# XmegaA4U_v1.net
KiCad netlist of a schematic drawn in EAGLE
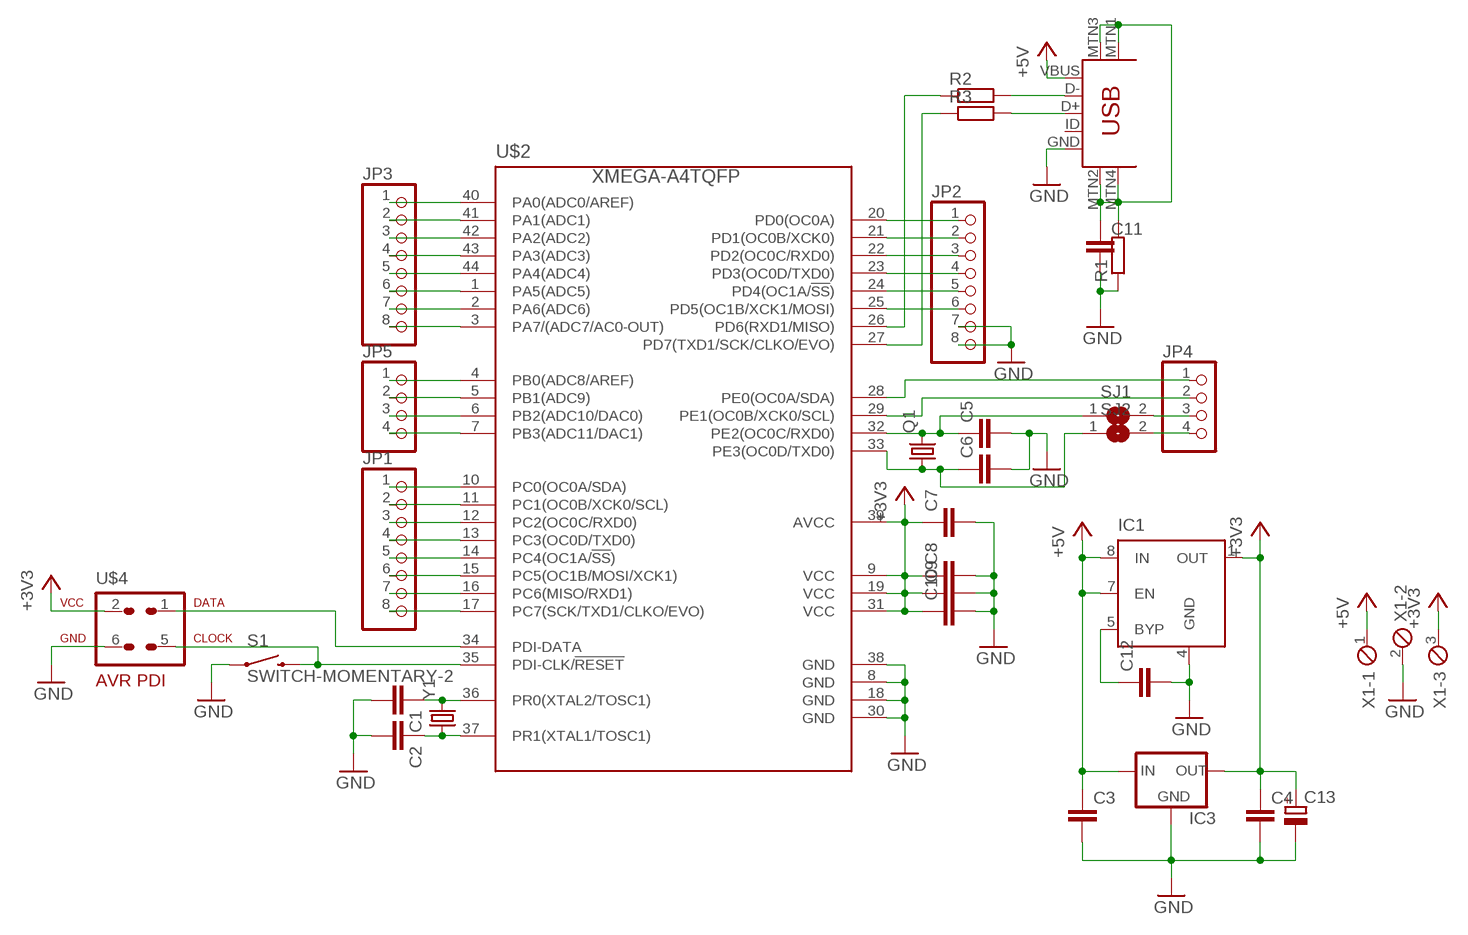
[diagram p0: schematic, sheet 1]

(export (version "E")
  (design (tool "Eeschema 10.0.6"))
  (components
    (comp (ref "C1")
      (value "C-EUC0603")
      (footprint "eagle-import:C0603")
      (libsource (lib "eagle-import") (part "C-EUC0603"))
    )
    (comp (ref "C2")
      (value "C-EUC0603")
      (footprint "eagle-import:C0603")
      (libsource (lib "eagle-import") (part "C-EUC0603"))
    )
    (comp (ref "C3")
      (value "C-EUC0805")
      (footprint "eagle-import:C0805")
      (libsource (lib "eagle-import") (part "C-EUC0805"))
    )
    (comp (ref "C4")
      (value "C-EUC0805")
      (footprint "eagle-import:C0805")
      (libsource (lib "eagle-import") (part "C-EUC0805"))
    )
    (comp (ref "C5")
      (value "C-EUC0603")
      (footprint "eagle-import:C0603")
      (libsource (lib "eagle-import") (part "C-EUC0603"))
    )
    (comp (ref "C6")
      (value "C-EUC0603")
      (footprint "eagle-import:C0603")
      (libsource (lib "eagle-import") (part "C-EUC0603"))
    )
    (comp (ref "C7")
      (value "C-EUC0603")
      (footprint "eagle-import:C0603")
      (libsource (lib "eagle-import") (part "C-EUC0603"))
    )
    (comp (ref "C8")
      (value "C-EUC0603")
      (footprint "eagle-import:C0603")
      (libsource (lib "eagle-import") (part "C-EUC0603"))
    )
    (comp (ref "C9")
      (value "C-EUC0603")
      (footprint "eagle-import:C0603")
      (libsource (lib "eagle-import") (part "C-EUC0603"))
    )
    (comp (ref "C10")
      (value "C-EUC0603")
      (footprint "eagle-import:C0603")
      (libsource (lib "eagle-import") (part "C-EUC0603"))
    )
    (comp (ref "C11")
      (value "C-EUC0603")
      (footprint "eagle-import:C0603")
      (libsource (lib "eagle-import") (part "C-EUC0603"))
    )
    (comp (ref "C12")
      (value "C-EUC0603")
      (footprint "eagle-import:C0603")
      (libsource (lib "eagle-import") (part "C-EUC0603"))
    )
    (comp (ref "C13")
      (value "CPOL-EUSMCB")
      (footprint "eagle-import:SMC_B")
      (libsource (lib "eagle-import") (part "CPOL-EUSMCB"))
    )
    (comp (ref "IC1")
      (value "TC1269")
      (footprint "eagle-import:MSOP08")
      (libsource (lib "eagle-import") (part "TC1269"))
    )
    (comp (ref "IC3")
      (value "VREG_3PIN_O-G-ITO92_MID")
      (footprint "eagle-import:TO92_MID")
      (libsource (lib "eagle-import") (part "VREG_3PIN_O-G-ITO92_MID"))
    )
    (comp (ref "JP1")
      (value "PINHD_FIXEDPAD_ROUND-1X8")
      (footprint "eagle-import:1X08_ROUND")
      (libsource (lib "eagle-import") (part "PINHD_FIXEDPAD_ROUND-1X8"))
    )
    (comp (ref "JP2")
      (value "PINHD_FIXEDPAD_ROUND-1X8")
      (footprint "eagle-import:1X08_ROUND")
      (libsource (lib "eagle-import") (part "PINHD_FIXEDPAD_ROUND-1X8"))
    )
    (comp (ref "JP3")
      (value "PINHD_FIXEDPAD_ROUND-1X8")
      (footprint "eagle-import:1X08_ROUND")
      (libsource (lib "eagle-import") (part "PINHD_FIXEDPAD_ROUND-1X8"))
    )
    (comp (ref "JP4")
      (value "PINHD_FIXEDPAD_ROUND-1X4")
      (footprint "eagle-import:1X04_ROUND")
      (libsource (lib "eagle-import") (part "PINHD_FIXEDPAD_ROUND-1X4"))
    )
    (comp (ref "JP5")
      (value "PINHD_FIXEDPAD_ROUND-1X4")
      (footprint "eagle-import:1X04_ROUND")
      (libsource (lib "eagle-import") (part "PINHD_FIXEDPAD_ROUND-1X4"))
    )
    (comp (ref "Q1")
      (value "CRYSTALTC26V")
      (footprint "eagle-import:TC26V")
      (libsource (lib "eagle-import") (part "CRYSTALTC26V"))
    )
    (comp (ref "R1")
      (value "R-EU_R0603")
      (footprint "eagle-import:R0603")
      (libsource (lib "eagle-import") (part "R-EU_R0603"))
    )
    (comp (ref "R2")
      (value "R-EU_R0603")
      (footprint "eagle-import:R0603")
      (libsource (lib "eagle-import") (part "R-EU_R0603"))
    )
    (comp (ref "R3")
      (value "R-EU_R0603")
      (footprint "eagle-import:R0603")
      (libsource (lib "eagle-import") (part "R-EU_R0603"))
    )
    (comp (ref "S1")
      (value "SWITCH-MOMENTARY-2")
      (footprint "eagle-import:TACTILE_SWITCH_TALL")
      (libsource (lib "eagle-import") (part "SWITCH-MOMENTARY-2"))
    )
    (comp (ref "SJ1")
      (value "SJ_SMALL")
      (footprint "eagle-import:SJ_2S-NO")
      (libsource (lib "eagle-import") (part "SJ_SMALL"))
    )
    (comp (ref "SJ2")
      (value "SJ_SMALL")
      (footprint "eagle-import:SJ_2S-NO")
      (libsource (lib "eagle-import") (part "SJ_SMALL"))
    )
    (comp (ref "U$1")
      (value "USB-MINIB-5PIN")
      (footprint "eagle-import:USB-MINIB")
      (libsource (lib "eagle-import") (part "USB-MINIB-5PIN"))
    )
    (comp (ref "U$2")
      (value "XMEGA-A4TQFP")
      (footprint "eagle-import:TQFP44")
      (libsource (lib "eagle-import") (part "XMEGA-A4TQFP"))
    )
    (comp (ref "U$4")
      (value "AVR-PDIVERT")
      (footprint "eagle-import:AVR-ISP-6")
      (libsource (lib "eagle-import") (part "AVR-PDIVERT"))
    )
    (comp (ref "X1")
      (value "MPT3")
      (footprint "eagle-import:3POL254")
      (libsource (lib "eagle-import") (part "MPT3"))
    )
    (comp (ref "Y1")
      (value "CRYSTAL5X3")
      (footprint "eagle-import:CRYSTAL-SMD-5X3")
      (libsource (lib "eagle-import") (part "CRYSTAL5X3"))
    )
  )
  (nets
    (net (code "1") (name "+3V3") (class "Default")
      (node (ref "C10") (pin "1") (pinfunction "1_1") (pintype "passive"))
      (node (ref "C13") (pin "+") (pinfunction "+_+") (pintype "passive"))
      (node (ref "C4") (pin "1") (pinfunction "1_1") (pintype "passive"))
      (node (ref "C7") (pin "1") (pinfunction "1_1") (pintype "passive"))
      (node (ref "C8") (pin "1") (pinfunction "1_1") (pintype "passive"))
      (node (ref "C9") (pin "1") (pinfunction "1_1") (pintype "passive"))
      (node (ref "IC1") (pin "1") (pinfunction "OUT_1") (pintype "output"))
      (node (ref "IC3") (pin "1") (pinfunction "OUT_1") (pintype "output"))
      (node (ref "U$2") (pin "19") (pinfunction "VCC_19") (pintype "power_in"))
      (node (ref "U$2") (pin "31") (pinfunction "VCC_31") (pintype "power_in"))
      (node (ref "U$2") (pin "39") (pinfunction "AVCC_39") (pintype "power_in"))
      (node (ref "U$2") (pin "9") (pinfunction "VCC_9") (pintype "power_in"))
      (node (ref "U$4") (pin "2") (pinfunction "2_2") (pintype "passive"))
      (node (ref "X1") (pin "3") (pinfunction "1_3") (pintype "passive"))
    )
    (net (code "2") (name "+5V") (class "Default")
      (node (ref "C3") (pin "1") (pinfunction "1_1") (pintype "passive"))
      (node (ref "IC1") (pin "7") (pinfunction "EN_7") (pintype "input"))
      (node (ref "IC1") (pin "8") (pinfunction "IN_8") (pintype "input"))
      (node (ref "IC3") (pin "3") (pinfunction "IN_3") (pintype "input"))
      (node (ref "U$1") (pin "VBUS") (pinfunction "VBUS_VBUS") (pintype "bidirectional"))
      (node (ref "X1") (pin "1") (pinfunction "1_1") (pintype "passive"))
    )
    (net (code "3") (name "GND") (class "Default")
      (node (ref "C1") (pin "2") (pinfunction "2_2") (pintype "passive"))
      (node (ref "C10") (pin "2") (pinfunction "2_2") (pintype "passive"))
      (node (ref "C11") (pin "2") (pinfunction "2_2") (pintype "passive"))
      (node (ref "C12") (pin "2") (pinfunction "2_2") (pintype "passive"))
      (node (ref "C13") (pin "-") (pinfunction "-_-") (pintype "passive"))
      (node (ref "C2") (pin "2") (pinfunction "2_2") (pintype "passive"))
      (node (ref "C3") (pin "2") (pinfunction "2_2") (pintype "passive"))
      (node (ref "C4") (pin "2") (pinfunction "2_2") (pintype "passive"))
      (node (ref "C5") (pin "2") (pinfunction "2_2") (pintype "passive"))
      (node (ref "C6") (pin "2") (pinfunction "2_2") (pintype "passive"))
      (node (ref "C7") (pin "2") (pinfunction "2_2") (pintype "passive"))
      (node (ref "C8") (pin "2") (pinfunction "2_2") (pintype "passive"))
      (node (ref "C9") (pin "2") (pinfunction "2_2") (pintype "passive"))
      (node (ref "IC1") (pin "4") (pinfunction "GND_4") (pintype "power_in"))
      (node (ref "IC3") (pin "2") (pinfunction "GND_2") (pintype "input"))
      (node (ref "JP2") (pin "7") (pinfunction "7_7") (pintype "passive"))
      (node (ref "JP2") (pin "8") (pinfunction "8_8") (pintype "passive"))
      (node (ref "R1") (pin "1") (pinfunction "1_1") (pintype "passive"))
      (node (ref "S1") (pin "A2") (pinfunction "1_A2") (pintype "passive"))
      (node (ref "U$1") (pin "GND") (pinfunction "GND_GND") (pintype "bidirectional"))
      (node (ref "U$2") (pin "18") (pinfunction "GND_18") (pintype "power_in"))
      (node (ref "U$2") (pin "30") (pinfunction "GND_30") (pintype "power_in"))
      (node (ref "U$2") (pin "38") (pinfunction "GND_38") (pintype "power_in"))
      (node (ref "U$2") (pin "8") (pinfunction "GND_8") (pintype "power_in"))
      (node (ref "U$4") (pin "6") (pinfunction "6_6") (pintype "passive"))
      (node (ref "X1") (pin "2") (pinfunction "1_2") (pintype "passive"))
    )
    (net (code "4") (name "Net-(IC1-BYP)") (class "Default")
      (node (ref "C12") (pin "1") (pinfunction "1_1") (pintype "passive"))
      (node (ref "IC1") (pin "5") (pinfunction "BYP_5") (pintype "passive"))
    )
    (net (code "5") (name "Net-(JP4-Pad3)") (class "Default")
      (node (ref "JP4") (pin "3") (pinfunction "3_3") (pintype "passive"))
      (node (ref "SJ1") (pin "2") (pinfunction "2_2") (pintype "passive"))
    )
    (net (code "6") (name "Net-(JP4-Pad4)") (class "Default")
      (node (ref "JP4") (pin "4") (pinfunction "4_4") (pintype "passive"))
      (node (ref "SJ2") (pin "2") (pinfunction "2_2") (pintype "passive"))
    )
    (net (code "7") (name "Net-(R2-Pad2)") (class "Default")
      (node (ref "R2") (pin "2") (pinfunction "2_2") (pintype "passive"))
      (node (ref "U$1") (pin "D-") (pinfunction "D-_D-") (pintype "bidirectional"))
    )
    (net (code "8") (name "Net-(R3-Pad2)") (class "Default")
      (node (ref "R3") (pin "2") (pinfunction "2_2") (pintype "passive"))
      (node (ref "U$1") (pin "D+") (pinfunction "D+_D+") (pintype "bidirectional"))
    )
    (net (code "9") (name "Net-(S1-2)") (class "Default")
      (node (ref "S1") (pin "B2") (pinfunction "2_B2") (pintype "passive"))
      (node (ref "U$2") (pin "35") (pinfunction "PDI-CLK/~{RESET}_35") (pintype "input"))
      (node (ref "U$4") (pin "5") (pinfunction "5_5") (pintype "passive"))
    )
    (net (code "10") (name "Net-(U$1-MTN1)") (class "Default")
      (node (ref "C11") (pin "1") (pinfunction "1_1") (pintype "passive"))
      (node (ref "R1") (pin "2") (pinfunction "2_2") (pintype "passive"))
      (node (ref "U$1") (pin "MTN1") (pinfunction "MTN2_MTN1") (pintype "bidirectional"))
      (node (ref "U$1") (pin "MTN2") (pinfunction "MTN3_MTN2") (pintype "bidirectional"))
      (node (ref "U$1") (pin "MTN3") (pinfunction "MTN1_MTN3") (pintype "bidirectional"))
      (node (ref "U$1") (pin "MTN4") (pinfunction "MTN4_MTN4") (pintype "bidirectional"))
    )
    (net (code "11") (name "Net-(U$2-PA0(ADC0{slash}AREF))") (class "Default")
      (node (ref "JP3") (pin "1") (pinfunction "1_1") (pintype "passive"))
      (node (ref "U$2") (pin "40") (pinfunction "PA0(ADC0/AREF)_40") (pintype "bidirectional"))
    )
    (net (code "12") (name "Net-(U$2-PA1(ADC1))") (class "Default")
      (node (ref "JP3") (pin "2") (pinfunction "2_2") (pintype "passive"))
      (node (ref "U$2") (pin "41") (pinfunction "PA1(ADC1)_41") (pintype "bidirectional"))
    )
    (net (code "13") (name "Net-(U$2-PA2(ADC2))") (class "Default")
      (node (ref "JP3") (pin "3") (pinfunction "3_3") (pintype "passive"))
      (node (ref "U$2") (pin "42") (pinfunction "PA2(ADC2)_42") (pintype "bidirectional"))
    )
    (net (code "14") (name "Net-(U$2-PA3(ADC3))") (class "Default")
      (node (ref "JP3") (pin "4") (pinfunction "4_4") (pintype "passive"))
      (node (ref "U$2") (pin "43") (pinfunction "PA3(ADC3)_43") (pintype "bidirectional"))
    )
    (net (code "15") (name "Net-(U$2-PA4(ADC4))") (class "Default")
      (node (ref "JP3") (pin "5") (pinfunction "5_5") (pintype "passive"))
      (node (ref "U$2") (pin "44") (pinfunction "PA4(ADC4)_44") (pintype "bidirectional"))
    )
    (net (code "16") (name "Net-(U$2-PA5(ADC5))") (class "Default")
      (node (ref "JP3") (pin "6") (pinfunction "6_6") (pintype "passive"))
      (node (ref "U$2") (pin "1") (pinfunction "PA5(ADC5)_1") (pintype "bidirectional"))
    )
    (net (code "17") (name "Net-(U$2-PA6(ADC6))") (class "Default")
      (node (ref "JP3") (pin "7") (pinfunction "7_7") (pintype "passive"))
      (node (ref "U$2") (pin "2") (pinfunction "PA6(ADC6)_2") (pintype "bidirectional"))
    )
    (net (code "18") (name "Net-(U$2-PA7{slash}(ADC7{slash}AC0-OUT))") (class "Default")
      (node (ref "JP3") (pin "8") (pinfunction "8_8") (pintype "passive"))
      (node (ref "U$2") (pin "3") (pinfunction "PA7/(ADC7/AC0-OUT)_3") (pintype "bidirectional"))
    )
    (net (code "19") (name "Net-(U$2-PB0(ADC8{slash}AREF))") (class "Default")
      (node (ref "JP5") (pin "1") (pinfunction "1_1") (pintype "passive"))
      (node (ref "U$2") (pin "4") (pinfunction "PB0(ADC8/AREF)_4") (pintype "bidirectional"))
    )
    (net (code "20") (name "Net-(U$2-PB1(ADC9))") (class "Default")
      (node (ref "JP5") (pin "2") (pinfunction "2_2") (pintype "passive"))
      (node (ref "U$2") (pin "5") (pinfunction "PB1(ADC9)_5") (pintype "bidirectional"))
    )
    (net (code "21") (name "Net-(U$2-PB2(ADC10{slash}DAC0))") (class "Default")
      (node (ref "JP5") (pin "3") (pinfunction "3_3") (pintype "passive"))
      (node (ref "U$2") (pin "6") (pinfunction "PB2(ADC10/DAC0)_6") (pintype "bidirectional"))
    )
    (net (code "22") (name "Net-(U$2-PB3(ADC11{slash}DAC1))") (class "Default")
      (node (ref "JP5") (pin "4") (pinfunction "4_4") (pintype "passive"))
      (node (ref "U$2") (pin "7") (pinfunction "PB3(ADC11/DAC1)_7") (pintype "bidirectional"))
    )
    (net (code "23") (name "Net-(U$2-PC0(OC0A{slash}SDA))") (class "Default")
      (node (ref "JP1") (pin "1") (pinfunction "1_1") (pintype "passive"))
      (node (ref "U$2") (pin "10") (pinfunction "PC0(OC0A/SDA)_10") (pintype "bidirectional"))
    )
    (net (code "24") (name "Net-(U$2-PC1(OC0B{slash}XCK0{slash}SCL))") (class "Default")
      (node (ref "JP1") (pin "2") (pinfunction "2_2") (pintype "passive"))
      (node (ref "U$2") (pin "11") (pinfunction "PC1(OC0B/XCK0/SCL)_11") (pintype "bidirectional"))
    )
    (net (code "25") (name "Net-(U$2-PC2(OC0C{slash}RXD0))") (class "Default")
      (node (ref "JP1") (pin "3") (pinfunction "3_3") (pintype "passive"))
      (node (ref "U$2") (pin "12") (pinfunction "PC2(OC0C/RXD0)_12") (pintype "bidirectional"))
    )
    (net (code "26") (name "Net-(U$2-PC3(OC0D{slash}TXD0))") (class "Default")
      (node (ref "JP1") (pin "4") (pinfunction "4_4") (pintype "passive"))
      (node (ref "U$2") (pin "13") (pinfunction "PC3(OC0D/TXD0)_13") (pintype "bidirectional"))
    )
    (net (code "27") (name "Net-(U$2-PC4(OC1A{slash}~{SS}))") (class "Default")
      (node (ref "JP1") (pin "5") (pinfunction "5_5") (pintype "passive"))
      (node (ref "U$2") (pin "14") (pinfunction "PC4(OC1A/~{SS})_14") (pintype "bidirectional"))
    )
    (net (code "28") (name "Net-(U$2-PC5(OC1B{slash}MOSI{slash}XCK1))") (class "Default")
      (node (ref "JP1") (pin "6") (pinfunction "6_6") (pintype "passive"))
      (node (ref "U$2") (pin "15") (pinfunction "PC5(OC1B/MOSI/XCK1)_15") (pintype "bidirectional"))
    )
    (net (code "29") (name "Net-(U$2-PC6(MISO{slash}RXD1))") (class "Default")
      (node (ref "JP1") (pin "7") (pinfunction "7_7") (pintype "passive"))
      (node (ref "U$2") (pin "16") (pinfunction "PC6(MISO/RXD1)_16") (pintype "bidirectional"))
    )
    (net (code "30") (name "Net-(U$2-PC7(SCK{slash}TXD1{slash}CLKO{slash}EVO))") (class "Default")
      (node (ref "JP1") (pin "8") (pinfunction "8_8") (pintype "passive"))
      (node (ref "U$2") (pin "17") (pinfunction "PC7(SCK/TXD1/CLKO/EVO)_17") (pintype "bidirectional"))
    )
    (net (code "31") (name "Net-(U$2-PD0(OC0A))") (class "Default")
      (node (ref "JP2") (pin "1") (pinfunction "1_1") (pintype "passive"))
      (node (ref "U$2") (pin "20") (pinfunction "PD0(OC0A)_20") (pintype "bidirectional"))
    )
    (net (code "32") (name "Net-(U$2-PD1(OC0B{slash}XCK0))") (class "Default")
      (node (ref "JP2") (pin "2") (pinfunction "2_2") (pintype "passive"))
      (node (ref "U$2") (pin "21") (pinfunction "PD1(OC0B/XCK0)_21") (pintype "bidirectional"))
    )
    (net (code "33") (name "Net-(U$2-PD2(OC0C{slash}RXD0))") (class "Default")
      (node (ref "JP2") (pin "3") (pinfunction "3_3") (pintype "passive"))
      (node (ref "U$2") (pin "22") (pinfunction "PD2(OC0C/RXD0)_22") (pintype "bidirectional"))
    )
    (net (code "34") (name "Net-(U$2-PD3(OC0D{slash}TXD0))") (class "Default")
      (node (ref "JP2") (pin "4") (pinfunction "4_4") (pintype "passive"))
      (node (ref "U$2") (pin "23") (pinfunction "PD3(OC0D/TXD0)_23") (pintype "bidirectional"))
    )
    (net (code "35") (name "Net-(U$2-PD4(OC1A{slash}~{SS}))") (class "Default")
      (node (ref "JP2") (pin "5") (pinfunction "5_5") (pintype "passive"))
      (node (ref "U$2") (pin "24") (pinfunction "PD4(OC1A/~{SS})_24") (pintype "bidirectional"))
    )
    (net (code "36") (name "Net-(U$2-PD5(OC1B{slash}XCK1{slash}MOSI))") (class "Default")
      (node (ref "JP2") (pin "6") (pinfunction "6_6") (pintype "passive"))
      (node (ref "U$2") (pin "25") (pinfunction "PD5(OC1B/XCK1/MOSI)_25") (pintype "bidirectional"))
    )
    (net (code "37") (name "Net-(U$2-PD6(RXD1{slash}MISO))") (class "Default")
      (node (ref "R2") (pin "1") (pinfunction "1_1") (pintype "passive"))
      (node (ref "U$2") (pin "26") (pinfunction "PD6(RXD1/MISO)_26") (pintype "bidirectional"))
    )
    (net (code "38") (name "Net-(U$2-PD7(TXD1{slash}SCK{slash}CLKO{slash}EVO))") (class "Default")
      (node (ref "R3") (pin "1") (pinfunction "1_1") (pintype "passive"))
      (node (ref "U$2") (pin "27") (pinfunction "PD7(TXD1/SCK/CLKO/EVO)_27") (pintype "bidirectional"))
    )
    (net (code "39") (name "Net-(U$2-PDI-DATA)") (class "Default")
      (node (ref "U$2") (pin "34") (pinfunction "PDI-DATA_34") (pintype "bidirectional"))
      (node (ref "U$4") (pin "1") (pinfunction "1_1") (pintype "passive"))
    )
    (net (code "40") (name "Net-(U$2-PE0(OC0A{slash}SDA))") (class "Default")
      (node (ref "JP4") (pin "1") (pinfunction "1_1") (pintype "passive"))
      (node (ref "U$2") (pin "28") (pinfunction "PE0(OC0A/SDA)_28") (pintype "bidirectional"))
    )
    (net (code "41") (name "Net-(U$2-PE1(OC0B{slash}XCK0{slash}SCL))") (class "Default")
      (node (ref "JP4") (pin "2") (pinfunction "2_2") (pintype "passive"))
      (node (ref "U$2") (pin "29") (pinfunction "PE1(OC0B/XCK0/SCL)_29") (pintype "bidirectional"))
    )
    (net (code "42") (name "Net-(U$2-PE2(OC0C{slash}RXD0))") (class "Default")
      (node (ref "C5") (pin "1") (pinfunction "1_1") (pintype "passive"))
      (node (ref "Q1") (pin "2") (pinfunction "2_2") (pintype "passive"))
      (node (ref "SJ1") (pin "1") (pinfunction "1_1") (pintype "passive"))
      (node (ref "U$2") (pin "32") (pinfunction "PE2(OC0C/RXD0)_32") (pintype "bidirectional"))
    )
    (net (code "43") (name "Net-(U$2-PE3(OC0D{slash}TXD0))") (class "Default")
      (node (ref "C6") (pin "1") (pinfunction "1_1") (pintype "passive"))
      (node (ref "Q1") (pin "1") (pinfunction "1_1") (pintype "passive"))
      (node (ref "SJ2") (pin "1") (pinfunction "1_1") (pintype "passive"))
      (node (ref "U$2") (pin "33") (pinfunction "PE3(OC0D/TXD0)_33") (pintype "bidirectional"))
    )
    (net (code "44") (name "Net-(U$2-PR0(XTAL2{slash}TOSC1))") (class "Default")
      (node (ref "C1") (pin "1") (pinfunction "1_1") (pintype "passive"))
      (node (ref "U$2") (pin "36") (pinfunction "PR0(XTAL2/TOSC1)_36") (pintype "bidirectional"))
      (node (ref "Y1") (pin "3") (pinfunction "2_3") (pintype "passive"))
    )
    (net (code "45") (name "Net-(U$2-PR1(XTAL1{slash}TOSC1))") (class "Default")
      (node (ref "C2") (pin "1") (pinfunction "1_1") (pintype "passive"))
      (node (ref "U$2") (pin "37") (pinfunction "PR1(XTAL1/TOSC1)_37") (pintype "bidirectional"))
      (node (ref "Y1") (pin "1") (pinfunction "1_1") (pintype "passive"))
    )
    (net (code "46") (name "unconnected-(U$1-PadID)") (class "Default")
      (node (ref "U$1") (pin "ID") (pinfunction "ID_ID") (pintype "bidirectional"))
    )
  )
)
